# AltiumSTM32_Schematic.net
KiCad netlist of a schematic drawn in Altium Designer
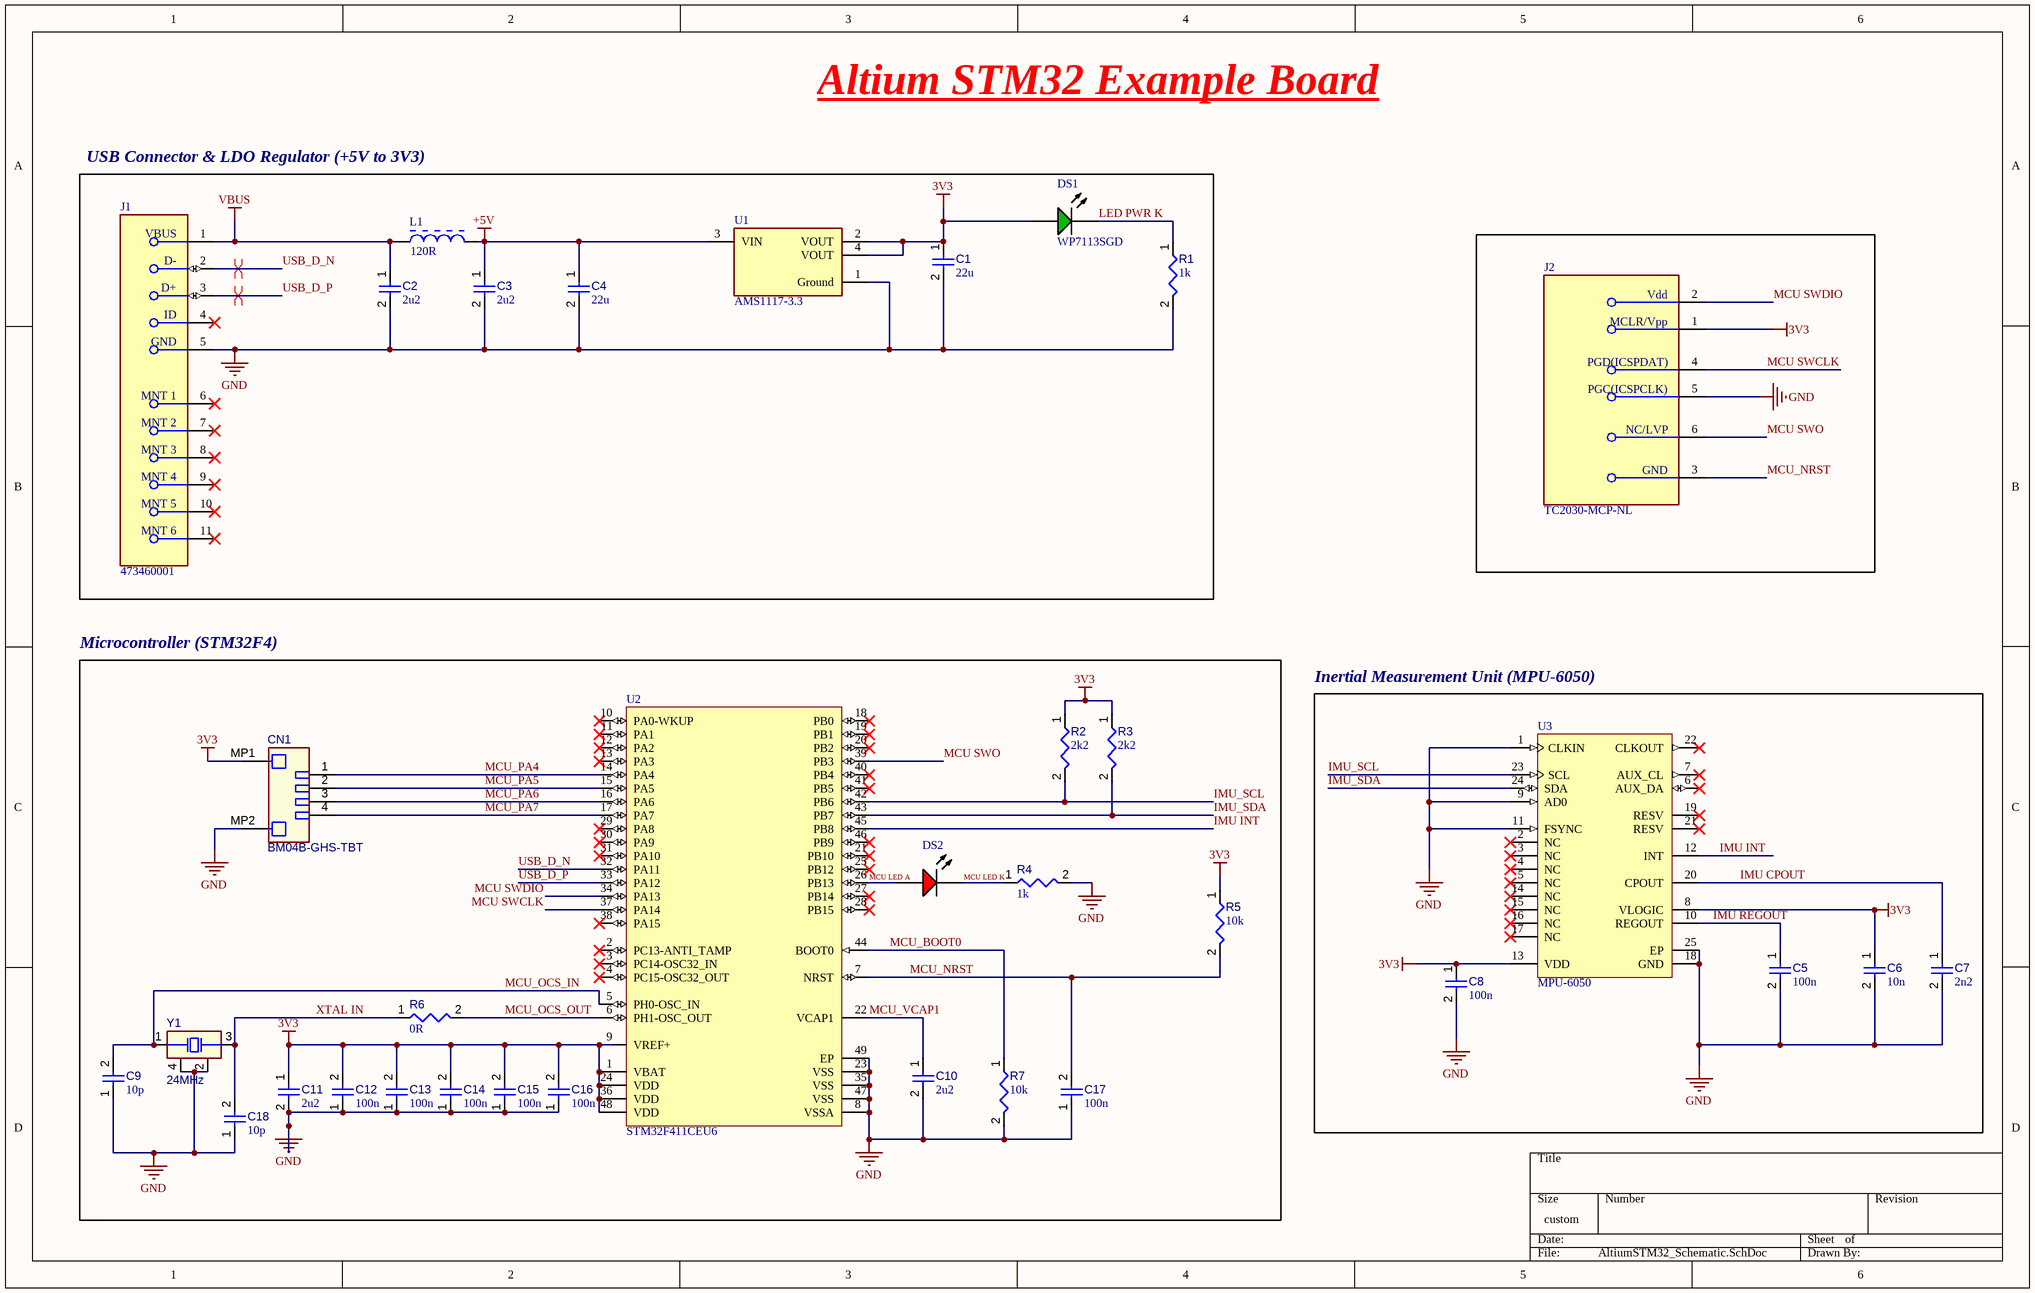
[diagram p0: AltiumSTM32_Schematic.SchDoc]

(export (version "E")
  (design (tool "Eeschema 10.0.6"))
  (components
    (comp (ref "C1")
      (value "22u")
      (footprint "CAPC0805(2012)145_L")
      (description "Chip Capacitor, 22µF +/-40%, 16V, 0805, Thickness 1.45 mm")
      (fields (field (name "TOLERANCE") "5%") (field (name "Comment") "Capacitor 22µF +/-40% 16V 0805"))
      (libsource (lib "Mazen129") (part "CAP-NP-2"))
    )
    (comp (ref "C2")
      (value "2u2")
      (footprint "CAPC1608X94X35NL15T15")
      (description "Chip Capacitor, 1 uF, +/- 10%, 16 V, 0603 (1608 Metric)")
      (fields (field (name "TOLERANCE") "10%") (field (name "Comment") "Capacitor 1 uF +/- 10% 16 V 0603"))
      (libsource (lib "Mazen129") (part "CAP-NP-2"))
    )
    (comp (ref "C3")
      (value "2u2")
      (footprint "CAPC1608X94X35NL15T15")
      (description "Chip Capacitor, 1 uF, +/- 10%, 16 V, 0603 (1608 Metric)")
      (fields (field (name "TOLERANCE") "10%") (field (name "Comment") "Capacitor 1 uF +/- 10% 16 V 0603"))
      (libsource (lib "Mazen129") (part "CAP-NP-2"))
    )
    (comp (ref "C4")
      (value "22u")
      (footprint "CAPC0805(2012)145_L")
      (description "Chip Capacitor, 22µF +/-40%, 16V, 0805, Thickness 1.45 mm")
      (fields (field (name "TOLERANCE") "5%") (field (name "Comment") "Capacitor 22µF +/-40% 16V 0805"))
      (libsource (lib "Mazen129") (part "CAP-NP-2"))
    )
    (comp (ref "C5")
      (value "100n")
      (footprint "CAPC1005X56X25LL10T15")
      (description "Chip Capacitor, 0.1 uF, +/- 5%, 16 V, 0402 (1005 Metric)")
      (fields (field (name "TOLERANCE") "5%") (field (name "Comment") "Capacitor 0.1 uF +/- 5% 16 V 0402"))
      (libsource (lib "Mazen129") (part "CAP-NP-2"))
    )
    (comp (ref "C6")
      (value "10n")
      (footprint "CAPC1005X56X25LL10T15")
      (description "Chip Capacitor, 0.1 uF, +/- 5%, 16 V, 0402 (1005 Metric)")
      (fields (field (name "TOLERANCE") "5%") (field (name "Comment") "Capacitor 0.1 uF +/- 5% 16 V 0402"))
      (libsource (lib "Mazen129") (part "CAP-NP-2"))
    )
    (comp (ref "C7")
      (value "2n2")
      (footprint "CAPC1005X56X25LL10T15")
      (description "Chip Capacitor, 0.1 uF, +/- 5%, 16 V, 0402 (1005 Metric)")
      (fields (field (name "TOLERANCE") "5%") (field (name "Comment") "Capacitor 0.1 uF +/- 5% 16 V 0402"))
      (libsource (lib "Mazen129") (part "CAP-NP-2"))
    )
    (comp (ref "C8")
      (value "100n")
      (footprint "CAPC1005X56X25LL10T15")
      (description "Chip Capacitor, 0.1 uF, +/- 5%, 16 V, 0402 (1005 Metric)")
      (fields (field (name "TOLERANCE") "5%") (field (name "Comment") "Capacitor 0.1 uF +/- 5% 16 V 0402"))
      (libsource (lib "Mazen129") (part "CAP-NP-2"))
    )
    (comp (ref "C9")
      (value "10p")
      (footprint "CAPC1005X56X25NL10T15")
      (description "Chip Capacitor, 6.8 nF, +/- 10%, 16 V, 0402 (1005 Metric)")
      (fields (field (name "TOLERANCE") "10%") (field (name "Comment") "Capacitor 6.8 nF +/- 10% 16 V 0402"))
      (libsource (lib "Mazen129") (part "CAP-NP-2"))
    )
    (comp (ref "C10")
      (value "2u2")
      (footprint "CAPC1608X94X35NL15T15")
      (description "Chip Capacitor, 1 uF, +/- 10%, 16 V, 0603 (1608 Metric)")
      (fields (field (name "TOLERANCE") "10%") (field (name "Comment") "Capacitor 1 uF +/- 10% 16 V 0603"))
      (libsource (lib "Mazen129") (part "CAP-NP-2"))
    )
    (comp (ref "C11")
      (value "2u2")
      (footprint "CAPC1608X94X35NL15T15")
      (description "Chip Capacitor, 1 uF, +/- 10%, 16 V, 0603 (1608 Metric)")
      (fields (field (name "TOLERANCE") "10%") (field (name "Comment") "Capacitor 1 uF +/- 10% 16 V 0603"))
      (libsource (lib "Mazen129") (part "CAP-NP-2"))
    )
    (comp (ref "C12")
      (value "100n")
      (footprint "CAPC1005X56X25LL10T15")
      (description "Chip Capacitor, 0.1 uF, +/- 5%, 16 V, 0402 (1005 Metric)")
      (fields (field (name "TOLERANCE") "5%") (field (name "Comment") "Capacitor 0.1 uF +/- 5% 16 V 0402"))
      (libsource (lib "Mazen129") (part "CAP-NP-2"))
    )
    (comp (ref "C13")
      (value "100n")
      (footprint "CAPC1005X56X25LL10T15")
      (description "Chip Capacitor, 0.1 uF, +/- 5%, 16 V, 0402 (1005 Metric)")
      (fields (field (name "TOLERANCE") "5%") (field (name "Comment") "Capacitor 0.1 uF +/- 5% 16 V 0402"))
      (libsource (lib "Mazen129") (part "CAP-NP-2"))
    )
    (comp (ref "C14")
      (value "100n")
      (footprint "CAPC1005X56X25LL10T15")
      (description "Chip Capacitor, 0.1 uF, +/- 5%, 16 V, 0402 (1005 Metric)")
      (fields (field (name "TOLERANCE") "5%") (field (name "Comment") "Capacitor 0.1 uF +/- 5% 16 V 0402"))
      (libsource (lib "Mazen129") (part "CAP-NP-2"))
    )
    (comp (ref "C15")
      (value "100n")
      (footprint "CAPC1005X56X25LL10T15")
      (description "Chip Capacitor, 0.1 uF, +/- 5%, 16 V, 0402 (1005 Metric)")
      (fields (field (name "TOLERANCE") "5%") (field (name "Comment") "Capacitor 0.1 uF +/- 5% 16 V 0402"))
      (libsource (lib "Mazen129") (part "CAP-NP-2"))
    )
    (comp (ref "C16")
      (value "100n")
      (footprint "CAPC1005X56X25LL10T15")
      (description "Chip Capacitor, 0.1 uF, +/- 5%, 16 V, 0402 (1005 Metric)")
      (fields (field (name "TOLERANCE") "5%") (field (name "Comment") "Capacitor 0.1 uF +/- 5% 16 V 0402"))
      (libsource (lib "Mazen129") (part "CAP-NP-2"))
    )
    (comp (ref "C17")
      (value "100n")
      (footprint "CAPC1005X56X25LL10T15")
      (description "Chip Capacitor, 0.1 uF, +/- 5%, 16 V, 0402 (1005 Metric)")
      (fields (field (name "TOLERANCE") "5%") (field (name "Comment") "Capacitor 0.1 uF +/- 5% 16 V 0402"))
      (libsource (lib "Mazen129") (part "CAP-NP-2"))
    )
    (comp (ref "C18")
      (value "10p")
      (footprint "CAPC1005X56X25NL10T15")
      (description "Chip Capacitor, 6.8 nF, +/- 10%, 16 V, 0402 (1005 Metric)")
      (fields (field (name "TOLERANCE") "10%") (field (name "Comment") "Capacitor 6.8 nF +/- 10% 16 V 0402"))
      (libsource (lib "Mazen129") (part "CAP-NP-2"))
    )
    (comp (ref "CN1")
      (value "BM04B-GHS-TBT")
      (footprint "JST-BM04B-GHS-TBT_V")
      (description "Header, Pitch 1.25 mm, 1 x 4 Position, Height 4.05 mm, -25 to 85 degC")
      (libsource (lib "Mazen129") (part "CMP-00071-3"))
    )
    (comp (ref "DS1")
      (value "WP7113SGD")
      (footprint "KING-WP7113SGD_V")
      (description "LED Green, 62.5 mW, 25 mA, -40 to 85 degC, 2-Pin THD, RoHS, Bulk")
      (fields (field (name "MANUFACTURER") "Kingbright") (field (name "POWER") "62.5mW"))
      (libsource (lib "Mazen129") (part "LED-GREEN-AK-2"))
    )
    (comp (ref "DS2")
      (value "UR502DC")
      (footprint "CGX-UR502DC")
      (description "Red LED, 80 mW, 30 mA, -25 to 85 degC, 2-Pin THD")
      (fields (field (name "POWER") "80mW") (field (name "MANUFACTURER") "Shenzhen CGX"))
      (libsource (lib "Mazen129") (part "LED-RED-AK-2"))
    )
    (comp (ref "J1")
      (value "473460001")
      (footprint "FP-473460001-MFG")
      (description "CONN RCPT USB2.0 MICRO B SMD R/A")
      (fields
        (field (name "OCTOPART") "https://octopart.com/47346-0001-molex-7164928")
        (field (name "MANUFACTURER") "Molex")
      )
      (libsource (lib "Altium Content Vault") (part "53ae1f1d9b557310b43ca686e5bb76a"))
    )
    (comp (ref "J2")
      (value "TC2030-MCP-NL")
      (footprint "FP-TC2030-MCP-NL-MFG")
      (description "CABLE TAG-CONNECT IN-CIRCUIT")
      (libsource (lib "Altium Content Vault") (part "da277a6d6cd793b3b4415b302df1337"))
    )
    (comp (ref "L1")
      (value "120R")
      (footprint "MURA-BLM18-F-H1-CHIP-2_V")
      (fields (field (name "TOLERANCE") "25%") (field (name "MANUFACTURER") "Murata"))
      (libsource (lib "Mazen129") (part "IND-FB-2"))
    )
    (comp (ref "R1")
      (value "1k")
      (footprint "RESC0402(1005)_L")
      (description "Chip Resistor, 9,1 kOhms, +/-5 %, 63 mW, -55 to 155 degC, 0402")
      (fields (field (name "POWER") "63mW") (field (name "TOLERANCE") "5%"))
      (libsource (lib "Mazen129") (part "RES-2"))
    )
    (comp (ref "R2")
      (value "2k2")
      (footprint "RESC0402(1005)_L")
      (description "Chip Resistor, 9,1 kOhms, +/-5 %, 63 mW, -55 to 155 degC, 0402")
      (fields (field (name "POWER") "63mW") (field (name "TOLERANCE") "5%"))
      (libsource (lib "Mazen129") (part "RES-2"))
    )
    (comp (ref "R3")
      (value "2k2")
      (footprint "RESC0402(1005)_L")
      (description "Chip Resistor, 9,1 kOhms, +/-5 %, 63 mW, -55 to 155 degC, 0402")
      (fields (field (name "POWER") "63mW") (field (name "TOLERANCE") "5%"))
      (libsource (lib "Mazen129") (part "RES-2"))
    )
    (comp (ref "R4")
      (value "1k")
      (footprint "RESC0402(1005)_L")
      (description "Chip Resistor, 9,1 kOhms, +/-5 %, 63 mW, -55 to 155 degC, 0402")
      (fields (field (name "POWER") "63mW") (field (name "TOLERANCE") "5%"))
      (libsource (lib "Mazen129") (part "RES-2"))
    )
    (comp (ref "R5")
      (value "10k")
      (footprint "RESC0402(1005)_L")
      (description "Chip Resistor, 9,1 kOhms, +/-5 %, 63 mW, -55 to 155 degC, 0402")
      (fields (field (name "POWER") "63mW") (field (name "TOLERANCE") "5%"))
      (libsource (lib "Mazen129") (part "RES-2"))
    )
    (comp (ref "R6")
      (value "0R")
      (footprint "RESC0402(1005)_L")
      (description "43K2 0.063W 1% 0402 (1005 Metric)  SMD")
      (fields (field (name "POWER") "63mW") (field (name "TOLERANCE") "1%"))
      (libsource (lib "Mazen129") (part "43D2KR2F"))
    )
    (comp (ref "R7")
      (value "10k")
      (footprint "RESC0402(1005)_L")
      (description "Chip Resistor, 9,1 kOhms, +/-5 %, 63 mW, -55 to 155 degC, 0402")
      (fields (field (name "POWER") "63mW") (field (name "TOLERANCE") "5%"))
      (libsource (lib "Mazen129") (part "RES-2"))
    )
    (comp (ref "U1")
      (value "AMS1117-3.3")
      (footprint "FP-AMS1117-IPC_C")
      (description "LDO Voltage Regulators 1A, 3.3V")
      (fields
        (field (name "OCTOPART") "https://octopart.com/ams1117-3.3-advanced+monolithic+systems-25899300")
        (field (name "MANUFACTURER") "Advanced Monolithic Systems")
      )
      (libsource (lib "Altium Content Vault") (part "8bdbb5f8e77002000e30dd2845d0354"))
    )
    (comp (ref "U2")
      (value "STM32F411CEU6")
      (footprint "STM-UFQFPN48_L")
      (libsource (lib "Altium Content Vault") (part "MC-ARM-STM32F411-UFQFPN48"))
    )
    (comp (ref "U3")
      (value "MPU-6050")
      (footprint "IS-QFN-24_V")
      (fields (field (name "MANUFACTURER") "InvenSense"))
      (libsource (lib "Altium Content Vault") (part "IS-MPU-6050-QFN-24"))
    )
    (comp (ref "Y1")
      (value "24MHz")
      (footprint "EPSON-FA-128_V")
      (description "Crystal, 24 MHz, +/- 10 ppm, -20 to 75 degC, 4-Pin SMD, RoHS, Tape and Reel")
      (libsource (lib "Mazen129") (part "CMP-00014-7"))
    )
  )
  (nets
    (net (code "1") (name "+5V") (class "Default")
      (node (ref "C3") (pin "1") (pinfunction "1_1") (pintype "passive"))
      (node (ref "C4") (pin "1") (pinfunction "1_1") (pintype "passive"))
      (node (ref "L1") (pin "2") (pinfunction "2_2") (pintype "passive"))
      (node (ref "U1") (pin "3") (pinfunction "VIN_3") (pintype "power_in"))
    )
    (net (code "2") (name "/IMU CPOUT") (class "Default")
      (node (ref "C7") (pin "1") (pinfunction "1_1") (pintype "passive"))
      (node (ref "U3") (pin "20") (pinfunction "CPOUT_20") (pintype "passive"))
    )
    (net (code "3") (name "/IMU INT") (class "Default")
      (node (ref "U2") (pin "45") (pinfunction "PB8_45") (pintype "bidirectional"))
      (node (ref "U3") (pin "12") (pinfunction "INT_12") (pintype "open_collector"))
    )
    (net (code "4") (name "/IMU REGOUT") (class "Default")
      (node (ref "C5") (pin "1") (pinfunction "1_1") (pintype "passive"))
      (node (ref "U3") (pin "10") (pinfunction "REGOUT_10") (pintype "passive"))
    )
    (net (code "5") (name "/IMU_SCL") (class "Default")
      (node (ref "R2") (pin "2") (pinfunction "2_2") (pintype "passive"))
      (node (ref "U2") (pin "42") (pinfunction "PB6_42") (pintype "bidirectional"))
      (node (ref "U3") (pin "23") (pinfunction "SCL_23") (pintype "input"))
    )
    (net (code "6") (name "/IMU_SDA") (class "Default")
      (node (ref "R3") (pin "2") (pinfunction "2_2") (pintype "passive"))
      (node (ref "U2") (pin "43") (pinfunction "PB7_43") (pintype "bidirectional"))
      (node (ref "U3") (pin "24") (pinfunction "SDA_24") (pintype "bidirectional"))
    )
    (net (code "7") (name "/LED PWR K") (class "Default")
      (node (ref "DS1") (pin "2") (pinfunction "K_2") (pintype "passive"))
      (node (ref "R1") (pin "1") (pinfunction "1_1") (pintype "passive"))
    )
    (net (code "8") (name "/MCU LED A") (class "Default")
      (node (ref "DS2") (pin "1") (pinfunction "A_1") (pintype "passive"))
      (node (ref "U2") (pin "26") (pinfunction "PB13_26") (pintype "bidirectional"))
    )
    (net (code "9") (name "/MCU LED K") (class "Default")
      (node (ref "DS2") (pin "2") (pinfunction "K_2") (pintype "passive"))
      (node (ref "R4") (pin "1") (pinfunction "1_1") (pintype "passive"))
    )
    (net (code "10") (name "/MCU SWCLK") (class "Default")
      (node (ref "J2") (pin "4") (pinfunction "PGD(ICSPDAT)_4") (pintype "passive"))
      (node (ref "U2") (pin "37") (pinfunction "PA14_37") (pintype "bidirectional"))
    )
    (net (code "11") (name "/MCU SWDIO") (class "Default")
      (node (ref "J2") (pin "2") (pinfunction "Vdd_2") (pintype "passive"))
      (node (ref "U2") (pin "34") (pinfunction "PA13_34") (pintype "bidirectional"))
    )
    (net (code "12") (name "/MCU SWO") (class "Default")
      (node (ref "J2") (pin "6") (pinfunction "NC/LVP_6") (pintype "passive"))
      (node (ref "U2") (pin "39") (pinfunction "PB3_39") (pintype "bidirectional"))
    )
    (net (code "13") (name "/MCU_BOOT0") (class "Default")
      (node (ref "R7") (pin "1") (pinfunction "1_1") (pintype "passive"))
      (node (ref "U2") (pin "44") (pinfunction "BOOT0_44") (pintype "input"))
    )
    (net (code "14") (name "/MCU_NRST") (class "Default")
      (node (ref "C17") (pin "2") (pinfunction "2_2") (pintype "passive"))
      (node (ref "J2") (pin "3") (pinfunction "GND_3") (pintype "passive"))
      (node (ref "R5") (pin "2") (pinfunction "2_2") (pintype "passive"))
      (node (ref "U2") (pin "7") (pinfunction "NRST_7") (pintype "bidirectional"))
    )
    (net (code "15") (name "/MCU_OCS_IN") (class "Default")
      (node (ref "C9") (pin "2") (pinfunction "2_2") (pintype "passive"))
      (node (ref "U2") (pin "5") (pinfunction "PH0-OSC_IN_5") (pintype "bidirectional"))
      (node (ref "Y1") (pin "1") (pinfunction "X1_1") (pintype "passive"))
    )
    (net (code "16") (name "/MCU_OCS_OUT") (class "Default")
      (node (ref "R6") (pin "2") (pinfunction "2_2") (pintype "passive"))
      (node (ref "U2") (pin "6") (pinfunction "PH1-OSC_OUT_6") (pintype "bidirectional"))
    )
    (net (code "17") (name "/MCU_PA4") (class "Default")
      (node (ref "CN1") (pin "1") (pinfunction "1_1") (pintype "passive"))
      (node (ref "U2") (pin "14") (pinfunction "PA4_14") (pintype "bidirectional"))
    )
    (net (code "18") (name "/MCU_PA5") (class "Default")
      (node (ref "CN1") (pin "2") (pinfunction "2_2") (pintype "passive"))
      (node (ref "U2") (pin "15") (pinfunction "PA5_15") (pintype "bidirectional"))
    )
    (net (code "19") (name "/MCU_PA6") (class "Default")
      (node (ref "CN1") (pin "3") (pinfunction "3_3") (pintype "passive"))
      (node (ref "U2") (pin "16") (pinfunction "PA6_16") (pintype "bidirectional"))
    )
    (net (code "20") (name "/MCU_PA7") (class "Default")
      (node (ref "CN1") (pin "4") (pinfunction "4_4") (pintype "passive"))
      (node (ref "U2") (pin "17") (pinfunction "PA7_17") (pintype "bidirectional"))
    )
    (net (code "21") (name "/MCU_VCAP1") (class "Default")
      (node (ref "C10") (pin "1") (pinfunction "1_1") (pintype "passive"))
      (node (ref "U2") (pin "22") (pinfunction "VCAP1_22") (pintype "passive"))
    )
    (net (code "22") (name "/USB_D_N") (class "Default")
      (node (ref "J1") (pin "2") (pinfunction "D-_2") (pintype "bidirectional"))
      (node (ref "U2") (pin "32") (pinfunction "PA11_32") (pintype "bidirectional"))
    )
    (net (code "23") (name "/USB_D_P") (class "Default")
      (node (ref "J1") (pin "3") (pinfunction "D+_3") (pintype "bidirectional"))
      (node (ref "U2") (pin "33") (pinfunction "PA12_33") (pintype "bidirectional"))
    )
    (net (code "24") (name "/XTAL IN") (class "Default")
      (node (ref "C18") (pin "2") (pinfunction "2_2") (pintype "passive"))
      (node (ref "R6") (pin "1") (pinfunction "1_1") (pintype "passive"))
      (node (ref "Y1") (pin "3") (pinfunction "X2_3") (pintype "passive"))
    )
    (net (code "25") (name "3V3") (class "Default")
      (node (ref "C1") (pin "1") (pinfunction "1_1") (pintype "passive"))
      (node (ref "C11") (pin "1") (pinfunction "1_1") (pintype "passive"))
      (node (ref "C12") (pin "2") (pinfunction "2_2") (pintype "passive"))
      (node (ref "C13") (pin "2") (pinfunction "2_2") (pintype "passive"))
      (node (ref "C14") (pin "2") (pinfunction "2_2") (pintype "passive"))
      (node (ref "C15") (pin "2") (pinfunction "2_2") (pintype "passive"))
      (node (ref "C16") (pin "2") (pinfunction "2_2") (pintype "passive"))
      (node (ref "C6") (pin "1") (pinfunction "1_1") (pintype "passive"))
      (node (ref "C8") (pin "1") (pinfunction "1_1") (pintype "passive"))
      (node (ref "CN1") (pin "MP1") (pinfunction "MP1_MP1") (pintype "passive"))
      (node (ref "DS1") (pin "1") (pinfunction "A_1") (pintype "passive"))
      (node (ref "J2") (pin "1") (pinfunction "MCLR/Vpp_1") (pintype "passive"))
      (node (ref "R2") (pin "1") (pinfunction "1_1") (pintype "passive"))
      (node (ref "R3") (pin "1") (pinfunction "1_1") (pintype "passive"))
      (node (ref "R5") (pin "1") (pinfunction "1_1") (pintype "passive"))
      (node (ref "U1") (pin "2") (pinfunction "VOUT_2") (pintype "passive"))
      (node (ref "U1") (pin "4") (pinfunction "VOUT_4") (pintype "passive"))
      (node (ref "U2") (pin "1") (pinfunction "VBAT_1") (pintype "power_in"))
      (node (ref "U2") (pin "24") (pinfunction "VDD_24") (pintype "power_in"))
      (node (ref "U2") (pin "36") (pinfunction "VDD_36") (pintype "power_in"))
      (node (ref "U2") (pin "48") (pinfunction "VDD_48") (pintype "power_in"))
      (node (ref "U2") (pin "9") (pinfunction "VREF+_9") (pintype "power_in"))
      (node (ref "U3") (pin "13") (pinfunction "VDD_13") (pintype "power_in"))
      (node (ref "U3") (pin "8") (pinfunction "VLOGIC_8") (pintype "power_in"))
    )
    (net (code "26") (name "GND") (class "Default")
      (node (ref "C1") (pin "2") (pinfunction "2_2") (pintype "passive"))
      (node (ref "C10") (pin "2") (pinfunction "2_2") (pintype "passive"))
      (node (ref "C11") (pin "2") (pinfunction "2_2") (pintype "passive"))
      (node (ref "C12") (pin "1") (pinfunction "1_1") (pintype "passive"))
      (node (ref "C13") (pin "1") (pinfunction "1_1") (pintype "passive"))
      (node (ref "C14") (pin "1") (pinfunction "1_1") (pintype "passive"))
      (node (ref "C15") (pin "1") (pinfunction "1_1") (pintype "passive"))
      (node (ref "C16") (pin "1") (pinfunction "1_1") (pintype "passive"))
      (node (ref "C17") (pin "1") (pinfunction "1_1") (pintype "passive"))
      (node (ref "C18") (pin "1") (pinfunction "1_1") (pintype "passive"))
      (node (ref "C2") (pin "2") (pinfunction "2_2") (pintype "passive"))
      (node (ref "C3") (pin "2") (pinfunction "2_2") (pintype "passive"))
      (node (ref "C4") (pin "2") (pinfunction "2_2") (pintype "passive"))
      (node (ref "C5") (pin "2") (pinfunction "2_2") (pintype "passive"))
      (node (ref "C6") (pin "2") (pinfunction "2_2") (pintype "passive"))
      (node (ref "C7") (pin "2") (pinfunction "2_2") (pintype "passive"))
      (node (ref "C8") (pin "2") (pinfunction "2_2") (pintype "passive"))
      (node (ref "C9") (pin "1") (pinfunction "1_1") (pintype "passive"))
      (node (ref "CN1") (pin "MP2") (pinfunction "MP2_MP2") (pintype "passive"))
      (node (ref "J1") (pin "5") (pinfunction "GND_5") (pintype "power_in"))
      (node (ref "J2") (pin "5") (pinfunction "PGC(ICSPCLK)_5") (pintype "passive"))
      (node (ref "R1") (pin "2") (pinfunction "2_2") (pintype "passive"))
      (node (ref "R4") (pin "2") (pinfunction "2_2") (pintype "passive"))
      (node (ref "R7") (pin "2") (pinfunction "2_2") (pintype "passive"))
      (node (ref "U1") (pin "1") (pinfunction "Ground_1") (pintype "power_in"))
      (node (ref "U2") (pin "23") (pinfunction "VSS_23") (pintype "power_in"))
      (node (ref "U2") (pin "35") (pinfunction "VSS_35") (pintype "power_in"))
      (node (ref "U2") (pin "47") (pinfunction "VSS_47") (pintype "power_in"))
      (node (ref "U2") (pin "49") (pinfunction "EP_49") (pintype "power_in"))
      (node (ref "U2") (pin "8") (pinfunction "VSSA_8") (pintype "power_in"))
      (node (ref "U3") (pin "1") (pinfunction "CLKIN_1") (pintype "input"))
      (node (ref "U3") (pin "11") (pinfunction "FSYNC_11") (pintype "input"))
      (node (ref "U3") (pin "18") (pinfunction "GND_18") (pintype "power_in"))
      (node (ref "U3") (pin "25") (pinfunction "EP_25") (pintype "power_in"))
      (node (ref "U3") (pin "9") (pinfunction "AD0_9") (pintype "input"))
      (node (ref "Y1") (pin "2") (pinfunction "NC_2") (pintype "power_in"))
      (node (ref "Y1") (pin "4") (pinfunction "NC_4") (pintype "power_in"))
    )
    (net (code "27") (name "VBUS") (class "Default")
      (node (ref "C2") (pin "1") (pinfunction "1_1") (pintype "passive"))
      (node (ref "J1") (pin "1") (pinfunction "VBUS_1") (pintype "power_in"))
      (node (ref "L1") (pin "1") (pinfunction "1_1") (pintype "passive"))
    )
    (net (code "28") (name "unconnected-(J1-ID-Pad4)") (class "Default")
      (node (ref "J1") (pin "4") (pinfunction "ID_4") (pintype "passive+no_connect"))
    )
    (net (code "29") (name "unconnected-(J1-MNT_1-Pad6)") (class "Default")
      (node (ref "J1") (pin "6") (pinfunction "MNT_1_6") (pintype "passive+no_connect"))
    )
    (net (code "30") (name "unconnected-(J1-MNT_2-Pad7)") (class "Default")
      (node (ref "J1") (pin "7") (pinfunction "MNT_2_7") (pintype "passive+no_connect"))
    )
    (net (code "31") (name "unconnected-(J1-MNT_3-Pad8)") (class "Default")
      (node (ref "J1") (pin "8") (pinfunction "MNT_3_8") (pintype "passive+no_connect"))
    )
    (net (code "32") (name "unconnected-(J1-MNT_4-Pad9)") (class "Default")
      (node (ref "J1") (pin "9") (pinfunction "MNT_4_9") (pintype "passive+no_connect"))
    )
    (net (code "33") (name "unconnected-(J1-MNT_5-Pad10)") (class "Default")
      (node (ref "J1") (pin "10") (pinfunction "MNT_5_10") (pintype "passive+no_connect"))
    )
    (net (code "34") (name "unconnected-(J1-MNT_6-Pad11)") (class "Default")
      (node (ref "J1") (pin "11") (pinfunction "MNT_6_11") (pintype "passive+no_connect"))
    )
    (net (code "35") (name "unconnected-(U2-PA0-WKUP-Pad10)") (class "Default")
      (node (ref "U2") (pin "10") (pinfunction "PA0-WKUP_10") (pintype "bidirectional+no_connect"))
    )
    (net (code "36") (name "unconnected-(U2-PA1-Pad11)") (class "Default")
      (node (ref "U2") (pin "11") (pinfunction "PA1_11") (pintype "bidirectional+no_connect"))
    )
    (net (code "37") (name "unconnected-(U2-PA2-Pad12)") (class "Default")
      (node (ref "U2") (pin "12") (pinfunction "PA2_12") (pintype "bidirectional+no_connect"))
    )
    (net (code "38") (name "unconnected-(U2-PA3-Pad13)") (class "Default")
      (node (ref "U2") (pin "13") (pinfunction "PA3_13") (pintype "bidirectional+no_connect"))
    )
    (net (code "39") (name "unconnected-(U2-PA8-Pad29)") (class "Default")
      (node (ref "U2") (pin "29") (pinfunction "PA8_29") (pintype "bidirectional+no_connect"))
    )
    (net (code "40") (name "unconnected-(U2-PA9-Pad30)") (class "Default")
      (node (ref "U2") (pin "30") (pinfunction "PA9_30") (pintype "bidirectional+no_connect"))
    )
    (net (code "41") (name "unconnected-(U2-PA10-Pad31)") (class "Default")
      (node (ref "U2") (pin "31") (pinfunction "PA10_31") (pintype "bidirectional+no_connect"))
    )
    (net (code "42") (name "unconnected-(U2-PA15-Pad38)") (class "Default")
      (node (ref "U2") (pin "38") (pinfunction "PA15_38") (pintype "bidirectional+no_connect"))
    )
    (net (code "43") (name "unconnected-(U2-PB0-Pad18)") (class "Default")
      (node (ref "U2") (pin "18") (pinfunction "PB0_18") (pintype "bidirectional+no_connect"))
    )
    (net (code "44") (name "unconnected-(U2-PB1-Pad19)") (class "Default")
      (node (ref "U2") (pin "19") (pinfunction "PB1_19") (pintype "bidirectional+no_connect"))
    )
    (net (code "45") (name "unconnected-(U2-PB2-Pad20)") (class "Default")
      (node (ref "U2") (pin "20") (pinfunction "PB2_20") (pintype "bidirectional+no_connect"))
    )
    (net (code "46") (name "unconnected-(U2-PB4-Pad40)") (class "Default")
      (node (ref "U2") (pin "40") (pinfunction "PB4_40") (pintype "bidirectional+no_connect"))
    )
    (net (code "47") (name "unconnected-(U2-PB5-Pad41)") (class "Default")
      (node (ref "U2") (pin "41") (pinfunction "PB5_41") (pintype "bidirectional+no_connect"))
    )
    (net (code "48") (name "unconnected-(U2-PB9-Pad46)") (class "Default")
      (node (ref "U2") (pin "46") (pinfunction "PB9_46") (pintype "bidirectional+no_connect"))
    )
    (net (code "49") (name "unconnected-(U2-PB10-Pad21)") (class "Default")
      (node (ref "U2") (pin "21") (pinfunction "PB10_21") (pintype "bidirectional+no_connect"))
    )
    (net (code "50") (name "unconnected-(U2-PB12-Pad25)") (class "Default")
      (node (ref "U2") (pin "25") (pinfunction "PB12_25") (pintype "bidirectional+no_connect"))
    )
    (net (code "51") (name "unconnected-(U2-PB14-Pad27)") (class "Default")
      (node (ref "U2") (pin "27") (pinfunction "PB14_27") (pintype "bidirectional+no_connect"))
    )
    (net (code "52") (name "unconnected-(U2-PB15-Pad28)") (class "Default")
      (node (ref "U2") (pin "28") (pinfunction "PB15_28") (pintype "bidirectional+no_connect"))
    )
    (net (code "53") (name "unconnected-(U2-PC13-ANTI_TAMP-Pad2)") (class "Default")
      (node (ref "U2") (pin "2") (pinfunction "PC13-ANTI_TAMP_2") (pintype "bidirectional+no_connect"))
    )
    (net (code "54") (name "unconnected-(U2-PC14-OSC32_IN-Pad3)") (class "Default")
      (node (ref "U2") (pin "3") (pinfunction "PC14-OSC32_IN_3") (pintype "bidirectional+no_connect"))
    )
    (net (code "55") (name "unconnected-(U2-PC15-OSC32_OUT-Pad4)") (class "Default")
      (node (ref "U2") (pin "4") (pinfunction "PC15-OSC32_OUT_4") (pintype "bidirectional+no_connect"))
    )
    (net (code "56") (name "unconnected-(U3-AUX_CL-Pad7)") (class "Default")
      (node (ref "U3") (pin "7") (pinfunction "AUX_CL_7") (pintype "output+no_connect"))
    )
    (net (code "57") (name "unconnected-(U3-AUX_DA-Pad6)") (class "Default")
      (node (ref "U3") (pin "6") (pinfunction "AUX_DA_6") (pintype "bidirectional+no_connect"))
    )
    (net (code "58") (name "unconnected-(U3-CLKOUT-Pad22)") (class "Default")
      (node (ref "U3") (pin "22") (pinfunction "CLKOUT_22") (pintype "output+no_connect"))
    )
    (net (code "59") (name "unconnected-(U3-NC-Pad2)") (class "Default")
      (node (ref "U3") (pin "2") (pinfunction "NC_2") (pintype "passive+no_connect"))
    )
    (net (code "60") (name "unconnected-(U3-NC-Pad3)") (class "Default")
      (node (ref "U3") (pin "3") (pinfunction "NC_3") (pintype "passive+no_connect"))
    )
    (net (code "61") (name "unconnected-(U3-NC-Pad4)") (class "Default")
      (node (ref "U3") (pin "4") (pinfunction "NC_4") (pintype "passive+no_connect"))
    )
    (net (code "62") (name "unconnected-(U3-NC-Pad5)") (class "Default")
      (node (ref "U3") (pin "5") (pinfunction "NC_5") (pintype "passive+no_connect"))
    )
    (net (code "63") (name "unconnected-(U3-NC-Pad14)") (class "Default")
      (node (ref "U3") (pin "14") (pinfunction "NC_14") (pintype "passive+no_connect"))
    )
    (net (code "64") (name "unconnected-(U3-NC-Pad15)") (class "Default")
      (node (ref "U3") (pin "15") (pinfunction "NC_15") (pintype "passive+no_connect"))
    )
    (net (code "65") (name "unconnected-(U3-NC-Pad16)") (class "Default")
      (node (ref "U3") (pin "16") (pinfunction "NC_16") (pintype "passive+no_connect"))
    )
    (net (code "66") (name "unconnected-(U3-NC-Pad17)") (class "Default")
      (node (ref "U3") (pin "17") (pinfunction "NC_17") (pintype "passive+no_connect"))
    )
    (net (code "67") (name "unconnected-(U3-RESV-Pad19)") (class "Default")
      (node (ref "U3") (pin "19") (pinfunction "RESV_19") (pintype "passive+no_connect"))
    )
    (net (code "68") (name "unconnected-(U3-RESV-Pad21)") (class "Default")
      (node (ref "U3") (pin "21") (pinfunction "RESV_21") (pintype "passive+no_connect"))
    )
  )
)
